# Charger_BQ25713.net
KiCad netlist of a schematic drawn in Altium Designer
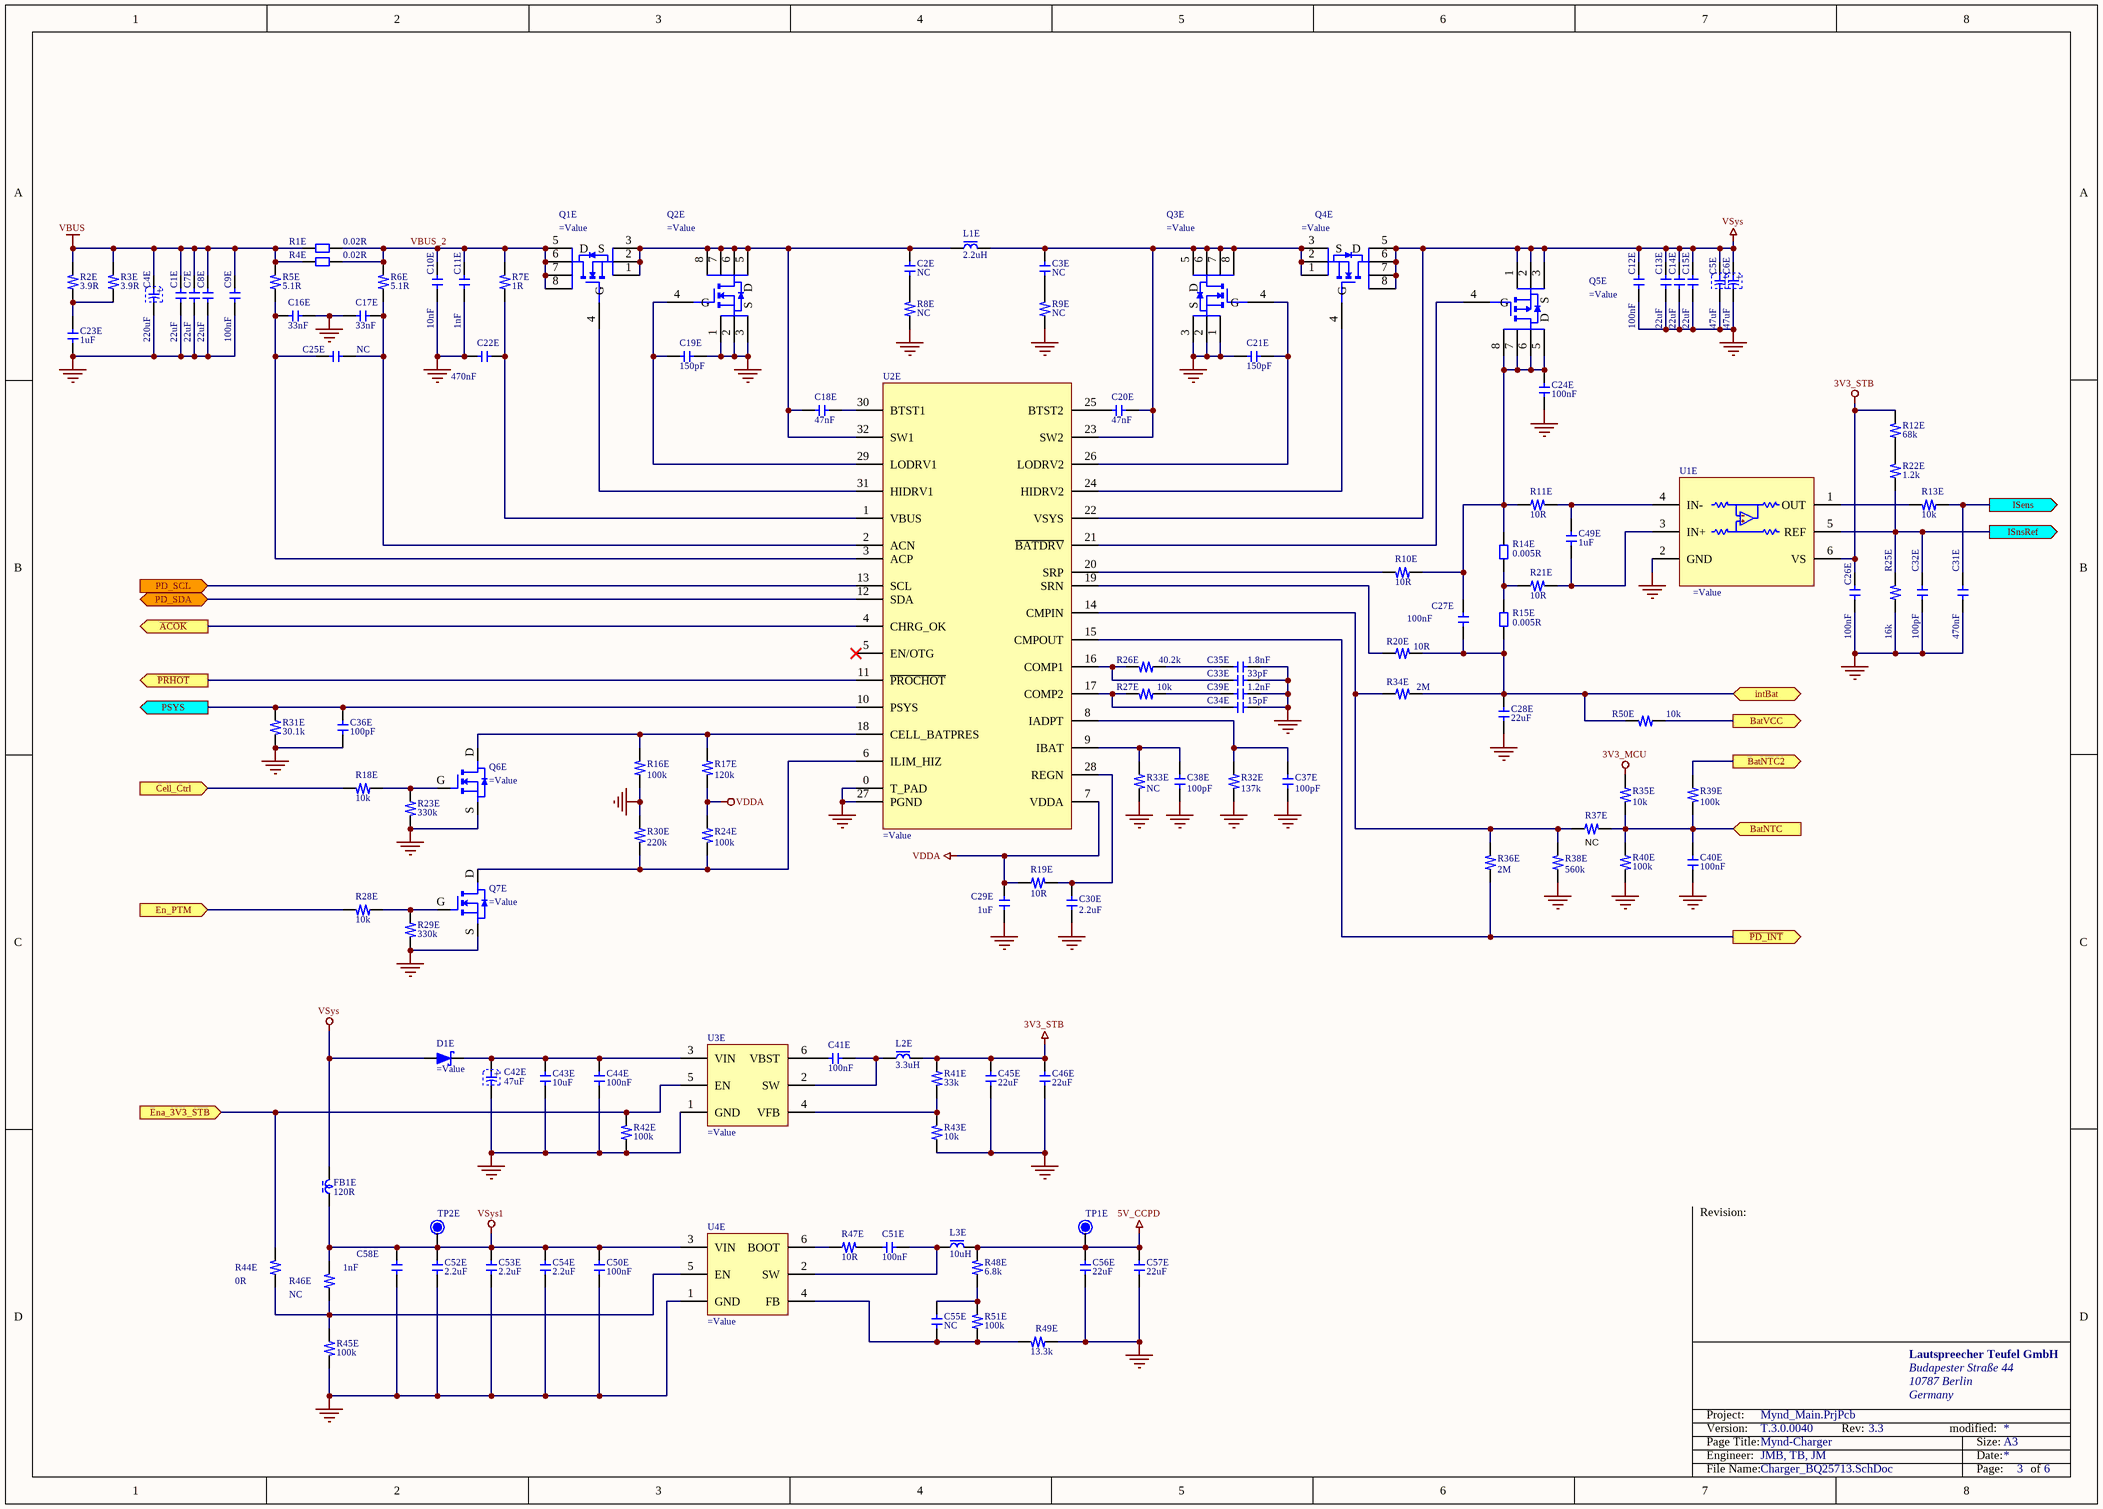
[diagram p0: Charger_BQ25713.SchDoc]

(export (version "E")
  (design (tool "Eeschema 10.0.6"))
  (components
    (comp (ref "C1E")
      (value "22uF")
      (footprint "C1206")
      (description "PSHF SMD M CAP 22uF 25V ±20% 1206 X5R")
      (fields (field (name "MANUFACTURER") "Multi Sourced") (field (name "TOLERANCE") "±20%"))
      (libsource (lib "altium-import") (part "root_3_CAP1_"))
    )
    (comp (ref "C2E")
      (value "NC")
      (footprint "C0603X80")
      (description "PSHF SMD M CAP 30pF 50V ±5% 0603 NPO")
      (fields (field (name "MANUFACTURER") "Multi Sourced") (field (name "TOLERANCE") "±5%"))
      (libsource (lib "altium-import") (part "root_1_CAP1_"))
    )
    (comp (ref "C3E")
      (value "NC")
      (footprint "C0603X80")
      (description "PSHF SMD M CAP 30pF 50V ±5% 0603 NPO")
      (fields (field (name "MANUFACTURER") "Multi Sourced") (field (name "TOLERANCE") "±5%"))
      (libsource (lib "altium-import") (part "root_1_CAP1_"))
    )
    (comp (ref "C4E")
      (value "220uF")
      (footprint "ECAP_SMD_800X1000")
      (description "PS SMD COND ELECT 220uF 35V ±20% 105℃")
      (fields (field (name "MANUFACTURER") "Multi-Sourced") (field (name "TOLERANCE") "±20%"))
      (libsource (lib "altium-import") (part "root_3_ECAP2_"))
    )
    (comp (ref "C5E")
      (value "47uF")
      (footprint "ECAP_SMD_630X540")
      (description "PS SMD COND ELECT 47uF 35V ±20% 105℃")
      (fields (field (name "MANUFACTURER") "Multi-Sourced") (field (name "TOLERANCE") "±20%"))
      (libsource (lib "altium-import") (part "root_3_ECAP2_"))
    )
    (comp (ref "C6E")
      (value "47uF")
      (footprint "ECAP_SMD_630X540")
      (description "PS SMD COND ELECT 47uF 35V ±20% 105℃")
      (fields (field (name "MANUFACTURER") "Multi-Sourced") (field (name "TOLERANCE") "±20%"))
      (libsource (lib "altium-import") (part "root_3_ECAP2_"))
    )
    (comp (ref "C7E")
      (value "22uF")
      (footprint "C1206")
      (description "PSHF SMD M CAP 22uF 25V ±20% 1206 X5R")
      (fields (field (name "MANUFACTURER") "Multi Sourced") (field (name "TOLERANCE") "±20%"))
      (libsource (lib "altium-import") (part "root_1_CAP1_"))
    )
    (comp (ref "C8E")
      (value "22uF")
      (footprint "C1206")
      (description "PSHF SMD M CAP 22uF 25V ±20% 1206 X5R")
      (fields (field (name "MANUFACTURER") "Multi Sourced") (field (name "TOLERANCE") "±20%"))
      (libsource (lib "altium-import") (part "root_1_CAP1_"))
    )
    (comp (ref "C9E")
      (value "100nF")
      (footprint "C0603X100")
      (description "PSHF SMD M CAP 100nF 50V ±10% 0603 X7R")
      (fields (field (name "MANUFACTURER") "Multi Sourced") (field (name "TOLERANCE") "±10%"))
      (libsource (lib "altium-import") (part "root_3_CAP1_"))
    )
    (comp (ref "C10E")
      (value "10nF")
      (footprint "C0603X100")
      (description "PSHF SMD M CAP 10nF 50V ±10% 0603 X7R")
      (fields (field (name "MANUFACTURER") "Multi Sourced") (field (name "TOLERANCE") "±10%"))
      (libsource (lib "altium-import") (part "root_1_CAP1_"))
    )
    (comp (ref "C11E")
      (value "1nF")
      (footprint "C0603X100")
      (description "PSHF SMD M CAP 1nF 50V ±10% 0603 X7R")
      (fields (field (name "MANUFACTURER") "Multi Sourced") (field (name "TOLERANCE") "±10%"))
      (libsource (lib "altium-import") (part "root_3_CAP1_"))
    )
    (comp (ref "C12E")
      (value "100nF")
      (footprint "C0603X100")
      (description "PSHF SMD M CAP 100nF 50V ±10% 0603 X7R")
      (fields (field (name "MANUFACTURER") "Multi Sourced") (field (name "TOLERANCE") "±10%"))
      (libsource (lib "altium-import") (part "root_1_CAP1_"))
    )
    (comp (ref "C13E")
      (value "22uF")
      (footprint "C1206")
      (description "PSHF SMD M CAP 22uF 25V ±20% 1206 X5R")
      (fields (field (name "MANUFACTURER") "Multi Sourced") (field (name "TOLERANCE") "±20%"))
      (libsource (lib "altium-import") (part "root_1_CAP1_"))
    )
    (comp (ref "C14E")
      (value "22uF")
      (footprint "C1206")
      (description "PSHF SMD M CAP 22uF 25V ±20% 1206 X5R")
      (fields (field (name "MANUFACTURER") "Multi Sourced") (field (name "TOLERANCE") "±20%"))
      (libsource (lib "altium-import") (part "root_1_CAP1_"))
    )
    (comp (ref "C15E")
      (value "22uF")
      (footprint "C1206")
      (description "PSHF SMD M CAP 22uF 25V ±20% 1206 X5R")
      (fields (field (name "MANUFACTURER") "Multi Sourced") (field (name "TOLERANCE") "±20%"))
      (libsource (lib "altium-import") (part "root_1_CAP1_"))
    )
    (comp (ref "C16E")
      (value "33nF")
      (footprint "C0603X100")
      (description "PSHF SMD M CAP 33nF 50V ±10% 0603 X7R")
      (fields (field (name "MANUFACTURER") "Multi Sourced") (field (name "TOLERANCE") "±10%"))
      (libsource (lib "altium-import") (part "root_2_CAP1_"))
    )
    (comp (ref "C17E")
      (value "33nF")
      (footprint "C0603X100")
      (description "PSHF SMD M CAP 33nF 50V ±10% 0603 X7R")
      (fields (field (name "MANUFACTURER") "Multi Sourced") (field (name "TOLERANCE") "±10%"))
      (libsource (lib "altium-import") (part "root_0_CAP1_"))
    )
    (comp (ref "C18E")
      (value "47nF")
      (footprint "C0603X100")
      (description "PSHF SMD M CAP 47nF 50V ±10% 0603 X7R")
      (fields (field (name "MANUFACTURER") "Multi Sourced") (field (name "TOLERANCE") "±10"))
      (libsource (lib "altium-import") (part "root_0_CAP1_"))
    )
    (comp (ref "C19E")
      (value "150pF")
      (footprint "C0603X80")
      (description "PSHF SMD M CAP 150pF 50V ±10% 0603 X7R")
      (fields (field (name "MANUFACTURER") "Multi Sourced") (field (name "TOLERANCE") "±10%"))
      (libsource (lib "altium-import") (part "root_2_CAP1_"))
    )
    (comp (ref "C20E")
      (value "47nF")
      (footprint "C0603X100")
      (description "PSHF SMD M CAP 47nF 50V ±10% 0603 X7R")
      (fields (field (name "MANUFACTURER") "Multi Sourced") (field (name "TOLERANCE") "±10"))
      (libsource (lib "altium-import") (part "root_0_CAP1_"))
    )
    (comp (ref "C21E")
      (value "150pF")
      (footprint "C0603X80")
      (description "PSHF SMD M CAP 150pF 50V ±10% 0603 X7R")
      (fields (field (name "MANUFACTURER") "Multi Sourced") (field (name "TOLERANCE") "±10%"))
      (libsource (lib "altium-import") (part "root_2_CAP1_"))
    )
    (comp (ref "C22E")
      (value "470nF")
      (footprint "C0603X100")
      (description "PSHF SMD M CAP 470nF 50V ±10% 0603 X7R")
      (fields (field (name "MANUFACTURER") "Multi Sourced") (field (name "TOLERANCE") "±10%"))
      (libsource (lib "altium-import") (part "root_0_CAP1_"))
    )
    (comp (ref "C23E")
      (value "1uF")
      (footprint "C0805_145")
      (description "PSHF SMD M CAP 1uF 50V ±10% 0805 X7R")
      (fields (field (name "MANUFACTURER") "Multi Sourced") (field (name "TOLERANCE") "±10%"))
      (libsource (lib "altium-import") (part "root_3_CAP1_"))
    )
    (comp (ref "C24E")
      (value "100nF")
      (footprint "C0603X100")
      (description "PSHF SMD M CAP 100nF 50V ±10% 0603 X7R")
      (fields (field (name "MANUFACTURER") "Multi Sourced") (field (name "TOLERANCE") "±10%"))
      (libsource (lib "altium-import") (part "root_3_CAP1_"))
    )
    (comp (ref "C25E")
      (value "NC")
      (footprint "C0603X100")
      (description "PSHF SMD M CAP 10nF 50V ±10% 0603 X7R")
      (fields (field (name "MANUFACTURER") "Multi Sourced") (field (name "TOLERANCE") "±10%"))
      (libsource (lib "altium-import") (part "root_0_CAP1_"))
    )
    (comp (ref "C26E")
      (value "100nF")
      (footprint "C0603X100")
      (description "PSHF SMD M CAP 100nF 50V ±10% 0603 X7R")
      (fields (field (name "MANUFACTURER") "Multi Sourced") (field (name "TOLERANCE") "±10%"))
      (libsource (lib "altium-import") (part "root_1_CAP1_"))
    )
    (comp (ref "C27E")
      (value "100nF")
      (footprint "C0603X100")
      (description "PSHF SMD M CAP 100nF 50V ±10% 0603 X7R")
      (fields (field (name "MANUFACTURER") "Multi Sourced") (field (name "TOLERANCE") "±10%"))
      (libsource (lib "altium-import") (part "root_3_CAP1_"))
    )
    (comp (ref "C28E")
      (value "22uF")
      (footprint "C1206")
      (description "PSHF SMD M CAP 22uF 25V ±20% 1206 X5R")
      (fields (field (name "MANUFACTURER") "Multi Sourced") (field (name "TOLERANCE") "±20%"))
      (libsource (lib "altium-import") (part "root_3_CAP1_"))
    )
    (comp (ref "C29E")
      (value "1uF")
      (footprint "C0603X105")
      (description "PSHF SMD M CAP 1uF 50V ±10% 0603 X7R")
      (fields (field (name "MANUFACTURER") "Multi Sourced") (field (name "TOLERANCE") "±10%"))
      (libsource (lib "altium-import") (part "root_3_CAP1_"))
    )
    (comp (ref "C30E")
      (value "2.2uF")
      (footprint "C0603X105")
      (description "PSHF SMD M CAP 2.2uF 25V ±10% 0603 X5R")
      (fields (field (name "MANUFACTURER") "Multi Sourced") (field (name "TOLERANCE") "±10%"))
      (libsource (lib "altium-import") (part "root_3_CAP1_"))
    )
    (comp (ref "C31E")
      (value "470nF")
      (footprint "C0603X100")
      (description "GPHF SMD M CAP 470nF 50V ±10% 0603 X5R")
      (fields (field (name "MANUFACTURER") "Multi Sourced") (field (name "TOLERANCE") "±10%"))
      (libsource (lib "altium-import") (part "root_1_CAP1_"))
    )
    (comp (ref "C32E")
      (value "100pF")
      (footprint "C0603X80")
      (description "PSHF SMD M CAP 100pF 50V ±10% 0603 X7R")
      (fields (field (name "MANUFACTURER") "Multi Sourced") (field (name "TOLERANCE") "±10%"))
      (libsource (lib "altium-import") (part "root_1_CAP1_"))
    )
    (comp (ref "C33E")
      (value "33pF")
      (footprint "C0603X80")
      (description "PSHF SMD M CAP 33pF 50V ±5% 0603 NPO")
      (fields (field (name "MANUFACTURER") "Multi Sourced") (field (name "TOLERANCE") "±5%"))
      (libsource (lib "altium-import") (part "root_0_mirrored_CAP1_"))
    )
    (comp (ref "C34E")
      (value "15pF")
      (footprint "C0603X80")
      (description "PSHF SMD M CAP 15pF 50V ±5% 0603 NPO")
      (fields (field (name "MANUFACTURER") "Multi Sourced") (field (name "TOLERANCE") "±5%"))
      (libsource (lib "altium-import") (part "root_2_CAP1_"))
    )
    (comp (ref "C35E")
      (value "1.8nF")
      (footprint "C0603X100")
      (description "PSHF SMD M CAP 1.8nF 50V ±10% 0603 X7R")
      (fields (field (name "MANUFACTURER") "Multi Sourced") (field (name "TOLERANCE") "±10%"))
      (libsource (lib "altium-import") (part "root_0_mirrored_CAP1_"))
    )
    (comp (ref "C36E")
      (value "100pF")
      (footprint "C0603X80")
      (description "PSHF SMD M CAP 100pF 50V ±10% 0603 X7R")
      (fields (field (name "MANUFACTURER") "Multi Sourced") (field (name "TOLERANCE") "±10%"))
      (libsource (lib "altium-import") (part "root_3_CAP1_"))
    )
    (comp (ref "C37E")
      (value "100pF")
      (footprint "C0603X80")
      (description "PSHF SMD M CAP 100pF 50V ±10% 0603 X7R")
      (fields (field (name "MANUFACTURER") "Multi Sourced") (field (name "TOLERANCE") "±10%"))
      (libsource (lib "altium-import") (part "root_3_CAP1_"))
    )
    (comp (ref "C38E")
      (value "100pF")
      (footprint "C0603X80")
      (description "PSHF SMD M CAP 100pF 50V ±10% 0603 X7R")
      (fields (field (name "MANUFACTURER") "Multi Sourced") (field (name "TOLERANCE") "±10%"))
      (libsource (lib "altium-import") (part "root_3_CAP1_"))
    )
    (comp (ref "C39E")
      (value "1.2nF")
      (footprint "C0402")
      (description "PSHF SMD M CAP 1.2nF 50V ±10% 0402 X7R")
      (fields (field (name "MANUFACTURER") "Multi Sourced") (field (name "TOLERANCE") "±10%"))
      (libsource (lib "altium-import") (part "root_0_CAP1_"))
    )
    (comp (ref "C40E")
      (value "100nF")
      (footprint "C0603X100")
      (description "PSHF SMD M CAP 100nF 50V ±10% 0603 X7R")
      (fields (field (name "MANUFACTURER") "Multi Sourced") (field (name "TOLERANCE") "±10%"))
      (libsource (lib "altium-import") (part "root_1_CAP1_"))
    )
    (comp (ref "C41E")
      (value "100nF")
      (footprint "C0603X100")
      (description "PSHF SMD M CAP 100nF 50V ±10% 0603 X7R")
      (fields (field (name "MANUFACTURER") "Multi Sourced") (field (name "TOLERANCE") "±10%"))
      (libsource (lib "altium-import") (part "root_0_CAP1_"))
    )
    (comp (ref "C42E")
      (value "47uF")
      (footprint "ECAP_SMD_630X540")
      (description "PS SMD COND ELECT 47uF 35V ±20% 105℃")
      (fields (field (name "MANUFACTURER") "Multi-Sourced") (field (name "TOLERANCE") "±20%"))
      (libsource (lib "altium-import") (part "root_3_ECAP2_"))
    )
    (comp (ref "C43E")
      (value "10uF")
      (footprint "C1206")
      (description "PSHF SMD M CAP 10uF 50V ±10% 1206 X5R")
      (fields (field (name "MANUFACTURER") "Multi Sourced") (field (name "TOLERANCE") "±10%"))
      (libsource (lib "altium-import") (part "root_3_CAP1_"))
    )
    (comp (ref "C44E")
      (value "100nF")
      (footprint "C0603X100")
      (description "PSHF SMD M CAP 100nF 50V ±10% 0603 X7R")
      (fields (field (name "MANUFACTURER") "Multi Sourced") (field (name "TOLERANCE") "±10%"))
      (libsource (lib "altium-import") (part "root_3_CAP1_"))
    )
    (comp (ref "C45E")
      (value "22uF")
      (footprint "C0805_145")
      (description "PSHF SMD M CAP 22uF 10V ±20% 0805 X5R")
      (fields (field (name "MANUFACTURER") "Multi Sourced") (field (name "TOLERANCE") "±20%"))
      (libsource (lib "altium-import") (part "root_3_CAP1_"))
    )
    (comp (ref "C46E")
      (value "22uF")
      (footprint "C0805_145")
      (description "PSHF SMD M CAP 22uF 10V ±20% 0805 X5R")
      (fields (field (name "MANUFACTURER") "Multi Sourced") (field (name "TOLERANCE") "±20%"))
      (libsource (lib "altium-import") (part "root_3_CAP1_"))
    )
    (comp (ref "C49E")
      (value "1uF")
      (footprint "C0603X105")
      (description "GPHF SMD M CAP 1uF 50V ±10% 0603 X7R")
      (fields (field (name "MANUFACTURER") "Multi Sourced") (field (name "TOLERANCE") "±10%"))
      (libsource (lib "altium-import") (part "root_3_CAP1_"))
    )
    (comp (ref "C50E")
      (value "100nF")
      (footprint "C0603X100")
      (description "PSHF SMD M CAP 100nF 50V ±10% 0603 X7R")
      (fields (field (name "MANUFACTURER") "Multi Sourced") (field (name "TOLERANCE") "±10%"))
      (libsource (lib "altium-import") (part "root_3_CAP1_"))
    )
    (comp (ref "C51E")
      (value "100nF")
      (footprint "C0603X100")
      (description "PSHF SMD M CAP 100nF 50V ±10% 0603 X7R")
      (fields (field (name "MANUFACTURER") "Multi Sourced") (field (name "TOLERANCE") "±10%"))
      (libsource (lib "altium-import") (part "root_2_CAP1_"))
    )
    (comp (ref "C52E")
      (value "2.2uF")
      (footprint "C0805_145")
      (description "PSHF SMD M CAP 2.2uF 50V ±10% 0805 X5R")
      (fields (field (name "MANUFACTURER") "Multi Sourced") (field (name "TOLERANCE") "±10%"))
      (libsource (lib "altium-import") (part "root_3_CAP1_"))
    )
    (comp (ref "C53E")
      (value "2.2uF")
      (footprint "C0805_145")
      (description "PSHF SMD M CAP 2.2uF 50V ±10% 0805 X5R")
      (fields (field (name "MANUFACTURER") "Multi Sourced") (field (name "TOLERANCE") "±10%"))
      (libsource (lib "altium-import") (part "root_3_CAP1_"))
    )
    (comp (ref "C54E")
      (value "2.2uF")
      (footprint "C0805_145")
      (description "PSHF SMD M CAP 2.2uF 50V ±10% 0805 X5R")
      (fields (field (name "MANUFACTURER") "Multi Sourced") (field (name "TOLERANCE") "±10%"))
      (libsource (lib "altium-import") (part "root_3_CAP1_"))
    )
    (comp (ref "C55E")
      (value "NC")
      (footprint "C0603X80")
      (description "PSHF SMD M CAP 15pF 50V ±5% 0603 NPO")
      (fields (field (name "MANUFACTURER") "Multi Sourced") (field (name "TOLERANCE") "±5%"))
      (libsource (lib "altium-import") (part "root_3_CAP1_"))
    )
    (comp (ref "C56E")
      (value "22uF")
      (footprint "C0805_145")
      (description "PSHF SMD M CAP 22uF 10V ±20% 0805 X5R")
      (fields (field (name "MANUFACTURER") "Multi Sourced") (field (name "TOLERANCE") "±20%"))
      (libsource (lib "altium-import") (part "root_3_CAP1_"))
    )
    (comp (ref "C57E")
      (value "22uF")
      (footprint "C0805_145")
      (description "PSHF SMD M CAP 22uF 10V ±20% 0805 X5R")
      (fields (field (name "MANUFACTURER") "Multi Sourced") (field (name "TOLERANCE") "±20%"))
      (libsource (lib "altium-import") (part "root_3_CAP1_"))
    )
    (comp (ref "C58E")
      (value "1nF")
      (footprint "C0603X105")
      (description "SMD M CAP 1nF 250V ±10% 0603 X7R")
      (fields (field (name "MANUFACTURER") "Multi Sourced") (field (name "TOLERANCE") "±10%"))
      (libsource (lib "altium-import") (part "root_3_CAP1_"))
    )
    (comp (ref "D1E")
      (value "~")
      (footprint "SOD-123")
      (description "PS SMD DIODE 2P SOD-123 B5819W CJ")
      (fields (field (name "MANUFACTURER") "[CJ]") (field (name "VOLTAGE") "40V"))
      (libsource (lib "altium-import") (part "root_0_DIODE_SCHOTTKY1_"))
    )
    (comp (ref "FB1E")
      (value "120R")
      (footprint "L0805")
      (description "GPHF SMD BEAD 120 OHM 5A 25% 0805")
      (fields (field (name "TOLERANCE") "1:25%") (field (name "MANUFACTURER") "Tai-Tech"))
      (libsource (lib "altium-import") (part "root_3_mirrored_Bead1_"))
    )
    (comp (ref "L1E")
      (value "2.2uH")
      (footprint "IND_SMD_YT_SQU_L118XW108XH40_A")
      (description "SMD INDUCTOR 2.2μH NORM")
      (fields (field (name "MANUFACTURER") "[CET CHAMPIONS]") (field (name "TOLERANCE") "7:20%"))
      (libsource (lib "altium-import") (part "root_0_INDUCTOR1_"))
    )
    (comp (ref "L2E")
      (value "3.3uH")
      (footprint "IND_SMD_SQU_L60XW60XH20")
      (description "SMD INDUCTOR 3.3μH 100KHz NORM")
      (fields (field (name "MANUFACTURER") "TSA") (field (name "TOLERANCE") "7:20%"))
      (libsource (lib "altium-import") (part "root_0_INDUCTOR1_"))
    )
    (comp (ref "L3E")
      (value "10uH")
      (footprint "IND_SMD_YT_SQU_L78XW70XH30")
      (description "GP SMD INDUCTOR 10uH 1MHz 1V NORM")
      (fields (field (name "MANUFACTURER") "[CHAMPIONS]") (field (name "VOLTAGE") "1V"))
      (libsource (lib "altium-import") (part "root_0_INDUCTOR1_"))
    )
    (comp (ref "Q1E")
      (value "~")
      (footprint "DFN8_500X600X100_127_A")
      (description "PSHF SMD FET 8P DFN8 AP4024GEMT-HF APEC")
      (fields (field (name "MANUFACTURER") "APEC") (field (name "VOLTAGE") "30V"))
      (libsource (lib "altium-import") (part "root_1_N-MOS2_8Pin_"))
    )
    (comp (ref "Q2E")
      (value "~")
      (footprint "DFN8_500X600X100_127_A")
      (description "PSHF SMD FET 8P DFN8 AP4024GEMT-HF APEC")
      (fields (field (name "MANUFACTURER") "APEC") (field (name "VOLTAGE") "30V"))
      (libsource (lib "altium-import") (part "root_0_N-MOS2_8Pin_"))
    )
    (comp (ref "Q3E")
      (value "~")
      (footprint "DFN8_500X600X100_127_A")
      (description "PSHF SMD FET 8P DFN8 AP4024GEMT-HF APEC")
      (fields (field (name "MANUFACTURER") "APEC") (field (name "VOLTAGE") "30V"))
      (libsource (lib "altium-import") (part "root_0_mirrored_N-MOS2_8Pin_"))
    )
    (comp (ref "Q4E")
      (value "~")
      (footprint "DFN8_500X600X100_127_A")
      (description "PSHF SMD FET 8P DFN8 AP4024GEMT-HF APEC")
      (fields (field (name "MANUFACTURER") "APEC") (field (name "VOLTAGE") "30V"))
      (libsource (lib "altium-import") (part "root_1_mirrored_N-MOS2_8Pin_"))
    )
    (comp (ref "Q5E")
      (value "~")
      (footprint "DFN8_500X600X100_127_A")
      (description "SMD FET 8P 30V PDFN5X6 SSC8039GN6 SSC")
      (fields (field (name "MANUFACTURER") "SSC") (field (name "VOLTAGE") "30"))
      (libsource (lib "altium-import") (part "root_2_mirrored_P-MOS2_8Pin_"))
    )
    (comp (ref "Q6E")
      (value "~")
      (footprint "SOT23-GSD")
      (description "GP SMD FET 3P SOT23 2N7002K CTE")
      (fields (field (name "MANUFACTURER") "CTE") (field (name "VOLTAGE") "60V"))
      (libsource (lib "altium-import") (part "root_0_N-MOS1_"))
    )
    (comp (ref "Q7E")
      (value "~")
      (footprint "SOT23-GSD")
      (description "GP SMD FET 3P SOT23 2N7002K CTE")
      (fields (field (name "MANUFACTURER") "CTE") (field (name "VOLTAGE") "60V"))
      (libsource (lib "altium-import") (part "root_0_N-MOS1_"))
    )
    (comp (ref "R1E")
      (value "0.02R")
      (footprint "R1206")
      (description "SMD METAL FILM RES. 20mohm 1W 1% 1206 WALTER")
      (fields (field (name "TOLERANCE") "1%") (field (name "MANUFACTURER") "WALTER"))
      (libsource (lib "altium-import") (part "root_0_RES4_"))
    )
    (comp (ref "R2E")
      (value "3.9R")
      (footprint "R0805")
      (description "SMD RES. 3.9Ohm 1/8W 1% 0805")
      (fields (field (name "TOLERANCE") "1%") (field (name "MANUFACTURER") "Multi-Sourced"))
      (libsource (lib "altium-import") (part "root_3_RES1_"))
    )
    (comp (ref "R3E")
      (value "3.9R")
      (footprint "R0805")
      (description "SMD RES. 3.9Ohm 1/8W 1% 0805")
      (fields (field (name "TOLERANCE") "1%") (field (name "MANUFACTURER") "Multi-Sourced"))
      (libsource (lib "altium-import") (part "root_3_RES1_"))
    )
    (comp (ref "R4E")
      (value "0.02R")
      (footprint "R1206")
      (description "SMD METAL FILM RES. 20mohm 1W 1% 1206 WALTER")
      (fields (field (name "TOLERANCE") "1%") (field (name "MANUFACTURER") "WALTER"))
      (libsource (lib "altium-import") (part "root_0_RES4_"))
    )
    (comp (ref "R5E")
      (value "5.1R")
      (footprint "R0603")
      (description "PS SMD RES. 5.1OHM 1/10W 1% 0603")
      (fields (field (name "TOLERANCE") "1%") (field (name "MANUFACTURER") "Multi-Sourced"))
      (libsource (lib "altium-import") (part "root_3_RES1_"))
    )
    (comp (ref "R6E")
      (value "5.1R")
      (footprint "R0603")
      (description "PS SMD RES. 5.1OHM 1/10W 1% 0603")
      (fields (field (name "TOLERANCE") "1%") (field (name "MANUFACTURER") "Multi-Sourced"))
      (libsource (lib "altium-import") (part "root_3_RES1_"))
    )
    (comp (ref "R7E")
      (value "1R")
      (footprint "R0603")
      (description "PS SMD RES. 1Ohm 1/10W 1% 0603")
      (fields (field (name "TOLERANCE") "1%") (field (name "MANUFACTURER") "Multi-Sourced"))
      (libsource (lib "altium-import") (part "root_3_RES1_"))
    )
    (comp (ref "R8E")
      (value "NC")
      (footprint "R0805")
      (description "PS SMD RES. 56OHM 1/8W 5% 0805")
      (fields (field (name "TOLERANCE") "5%") (field (name "MANUFACTURER") "Multi-Sourced"))
      (libsource (lib "altium-import") (part "root_3_RES1_"))
    )
    (comp (ref "R9E")
      (value "NC")
      (footprint "R0805")
      (description "PS SMD RES. 56OHM 1/8W 5% 0805")
      (fields (field (name "TOLERANCE") "5%") (field (name "MANUFACTURER") "Multi-Sourced"))
      (libsource (lib "altium-import") (part "root_3_RES1_"))
    )
    (comp (ref "R10E")
      (value "10R")
      (footprint "R0603")
      (description "PS SMD RES. 10OHM 1/10W 1% 0603")
      (fields (field (name "TOLERANCE") "1%") (field (name "MANUFACTURER") "Multi-Sourced"))
      (libsource (lib "altium-import") (part "root_0_RES1_"))
    )
    (comp (ref "R11E")
      (value "10R")
      (footprint "R0603")
      (description "GPHF SMD RES. 10OHM 1/10W 1% 0603")
      (fields (field (name "TOLERANCE") "1%") (field (name "MANUFACTURER") "Multi-Sourced"))
      (libsource (lib "altium-import") (part "root_2_mirrored_RES1_"))
    )
    (comp (ref "R12E")
      (value "68k")
      (footprint "R0603")
      (description "PS SMD RES. 68KOHM 1/10W 1% 0603")
      (fields (field (name "TOLERANCE") "1%") (field (name "MANUFACTURER") "Multi-Sourced"))
      (libsource (lib "altium-import") (part "root_1_mirrored_RES1_"))
    )
    (comp (ref "R13E")
      (value "10k")
      (footprint "R0603")
      (description "PS SMD RES. 10KOHM 1/10W 1% 0603")
      (fields (field (name "TOLERANCE") "1%") (field (name "MANUFACTURER") "Multi-Sourced"))
      (libsource (lib "altium-import") (part "root_0_mirrored_RES1_"))
    )
    (comp (ref "R14E")
      (value "0.005R")
      (footprint "R1206")
      (description "SMD METAL FILM RES. 5mohm 1W 1% 1206 WALTER")
      (fields (field (name "TOLERANCE") "1%") (field (name "MANUFACTURER") "WALTER"))
      (libsource (lib "altium-import") (part "root_1_RES4_"))
    )
    (comp (ref "R15E")
      (value "0.005R")
      (footprint "R1206")
      (description "SMD METAL FILM RES. 5mohm 1W 1% 1206 WALTER")
      (fields (field (name "TOLERANCE") "1%") (field (name "MANUFACTURER") "WALTER"))
      (libsource (lib "altium-import") (part "root_1_RES4_"))
    )
    (comp (ref "R16E")
      (value "100k")
      (footprint "R0603")
      (description "PS SMD RES. 100KOHM 1/10W 1% 0603")
      (fields (field (name "TOLERANCE") "1%") (field (name "MANUFACTURER") "Multi-Sourced"))
      (libsource (lib "altium-import") (part "root_3_RES1_"))
    )
    (comp (ref "R17E")
      (value "120k")
      (footprint "R0603")
      (description "PS SMD RES. 120Kohm 1/10W 1% 0603")
      (fields (field (name "TOLERANCE") "1%") (field (name "MANUFACTURER") "Multi-Sourced"))
      (libsource (lib "altium-import") (part "root_3_mirrored_RES1_"))
    )
    (comp (ref "R18E")
      (value "10k")
      (footprint "R0603")
      (description "PS SMD RES. 10KOHM 1/10W 1% 0603")
      (fields (field (name "TOLERANCE") "1%") (field (name "MANUFACTURER") "Multi-Sourced"))
      (libsource (lib "altium-import") (part "root_0_RES1_"))
    )
    (comp (ref "R19E")
      (value "10R")
      (footprint "R0603")
      (description "PS SMD RES. 10OHM 1/10W 1% 0603")
      (fields (field (name "TOLERANCE") "1%") (field (name "MANUFACTURER") "Multi-Sourced"))
      (libsource (lib "altium-import") (part "root_2_RES1_"))
    )
    (comp (ref "R20E")
      (value "10R")
      (footprint "R0603")
      (description "PS SMD RES. 10OHM 1/10W 1% 0603")
      (fields (field (name "TOLERANCE") "1%") (field (name "MANUFACTURER") "Multi-Sourced"))
      (libsource (lib "altium-import") (part "root_2_RES1_"))
    )
    (comp (ref "R21E")
      (value "10R")
      (footprint "R0603")
      (description "GPHF SMD RES. 10OHM 1/10W 1% 0603")
      (fields (field (name "TOLERANCE") "1%") (field (name "MANUFACTURER") "Multi-Sourced"))
      (libsource (lib "altium-import") (part "root_2_RES1_"))
    )
    (comp (ref "R22E")
      (value "1.2k")
      (footprint "R0603")
      (description "PS SMD RES. 1.2KOHM 1/10W 1% 0603")
      (fields (field (name "TOLERANCE") "1%") (field (name "MANUFACTURER") "Multi-Sourced"))
      (libsource (lib "altium-import") (part "root_1_mirrored_RES1_"))
    )
    (comp (ref "R23E")
      (value "330k")
      (footprint "R0603")
      (description "PS SMD RES. 330KOHM 1/10W 1% 0603")
      (fields (field (name "TOLERANCE") "1%") (field (name "MANUFACTURER") "Multi-Sourced"))
      (libsource (lib "altium-import") (part "root_1_RES1_"))
    )
    (comp (ref "R24E")
      (value "100k")
      (footprint "R0603")
      (description "PS SMD RES. 100KOHM 1/10W 1% 0603")
      (fields (field (name "TOLERANCE") "1%") (field (name "MANUFACTURER") "Multi-Sourced"))
      (libsource (lib "altium-import") (part "root_3_mirrored_RES1_"))
    )
    (comp (ref "R25E")
      (value "16k")
      (footprint "R0603")
      (description "GPHF SMD RES. 16KOHM 1/10W 1% 0603")
      (fields (field (name "TOLERANCE") "1%") (field (name "MANUFACTURER") "Multi-Sourced"))
      (libsource (lib "altium-import") (part "root_1_mirrored_RES1_"))
    )
    (comp (ref "R26E")
      (value "40.2k")
      (footprint "R0603")
      (description "SMD RES. 40.2KOhm 1/10W 1% 0603")
      (fields (field (name "TOLERANCE") "1%") (field (name "MANUFACTURER") "Multi-Sourced"))
      (libsource (lib "altium-import") (part "root_0_mirrored_RES1_"))
    )
    (comp (ref "R27E")
      (value "10k")
      (footprint "R0603")
      (description "PS SMD RES. 10KOHM 1/10W 1% 0603")
      (fields (field (name "TOLERANCE") "1%") (field (name "MANUFACTURER") "Multi-Sourced"))
      (libsource (lib "altium-import") (part "root_0_RES1_"))
    )
    (comp (ref "R28E")
      (value "10k")
      (footprint "R0603")
      (description "PS SMD RES. 10KOHM 1/10W 1% 0603")
      (fields (field (name "TOLERANCE") "1%") (field (name "MANUFACTURER") "Multi-Sourced"))
      (libsource (lib "altium-import") (part "root_0_RES1_"))
    )
    (comp (ref "R29E")
      (value "330k")
      (footprint "R0603")
      (description "PS SMD RES. 330KOHM 1/10W 1% 0603")
      (fields (field (name "TOLERANCE") "1%") (field (name "MANUFACTURER") "Multi-Sourced"))
      (libsource (lib "altium-import") (part "root_1_RES1_"))
    )
    (comp (ref "R30E")
      (value "220k")
      (footprint "R0603")
      (description "PS SMD RES. 220KOHM 1/10W 1% 0603")
      (fields (field (name "TOLERANCE") "1%") (field (name "MANUFACTURER") "Multi-Sourced"))
      (libsource (lib "altium-import") (part "root_1_RES1_"))
    )
    (comp (ref "R31E")
      (value "30.1k")
      (footprint "R0603")
      (description "PS SMD RES. 30.1KOHM 1/10W 1% 0603")
      (fields (field (name "TOLERANCE") "1%") (field (name "MANUFACTURER") "Multi-Sourced"))
      (libsource (lib "altium-import") (part "root_1_RES1_"))
    )
    (comp (ref "R32E")
      (value "137k")
      (footprint "R0603")
      (description "SMD RES. 137KOhm 1/10W 1% 0603")
      (fields (field (name "TOLERANCE") "1%") (field (name "MANUFACTURER") "Multi-Sourced"))
      (libsource (lib "altium-import") (part "root_1_RES1_"))
    )
    (comp (ref "R33E")
      (value "NC")
      (footprint "R0603")
      (description "PS SMD RES. 100KOHM 1/10W 1% 0603")
      (fields (field (name "TOLERANCE") "1%") (field (name "MANUFACTURER") "Multi-Sourced"))
      (libsource (lib "altium-import") (part "root_1_RES1_"))
    )
    (comp (ref "R34E")
      (value "2M")
      (footprint "R0603")
      (description "PS SMD RES. 2Mohm 1/10W 1% 0603")
      (fields (field (name "TOLERANCE") "1%") (field (name "MANUFACTURER") "Multi-Sourced"))
      (libsource (lib "altium-import") (part "root_2_RES1_"))
    )
    (comp (ref "R35E")
      (value "10k")
      (footprint "R0603")
      (description "PS SMD RES. 10KOHM 1/10W 1% 0603")
      (fields (field (name "TOLERANCE") "1%") (field (name "MANUFACTURER") "Multi-Sourced"))
      (libsource (lib "altium-import") (part "root_1_RES1_"))
    )
    (comp (ref "R36E")
      (value "2M")
      (footprint "R0603")
      (description "PS SMD RES. 2Mohm 1/10W 1% 0603")
      (fields (field (name "TOLERANCE") "1%") (field (name "MANUFACTURER") "Multi-Sourced"))
      (libsource (lib "altium-import") (part "root_3_RES1_"))
    )
    (comp (ref "R37E")
      (value "100k")
      (footprint "R0603")
      (description "PS SMD RES. 100KOHM 1/10W 1% 0603")
      (fields (field (name "TOLERANCE") "1%") (field (name "MANUFACTURER") "Multi-Sourced"))
      (libsource (lib "altium-import") (part "root_2_RES1_"))
    )
    (comp (ref "R38E")
      (value "560k")
      (footprint "R0603")
      (description "PS SMD RES. 560KOHM 1/10W 5% 0603")
      (fields (field (name "TOLERANCE") "1%") (field (name "MANUFACTURER") "Multi-Sourced"))
      (libsource (lib "altium-import") (part "root_3_RES1_"))
    )
    (comp (ref "R39E")
      (value "100k")
      (footprint "R0603")
      (description "PS SMD RES. 100KOHM 1/10W 1% 0603")
      (fields (field (name "TOLERANCE") "1%") (field (name "MANUFACTURER") "Multi-Sourced"))
      (libsource (lib "altium-import") (part "root_1_RES1_"))
    )
    (comp (ref "R40E")
      (value "100k")
      (footprint "R0603")
      (description "PS SMD RES. 100KOHM 1/10W 1% 0603")
      (fields (field (name "TOLERANCE") "1%") (field (name "MANUFACTURER") "Multi-Sourced"))
      (libsource (lib "altium-import") (part "root_1_RES1_"))
    )
    (comp (ref "R41E")
      (value "33k")
      (footprint "R0603")
      (description "PS SMD RES. 33KOHM 1/10W 1% 0603")
      (fields (field (name "TOLERANCE") "1%") (field (name "MANUFACTURER") "Multi-Sourced"))
      (libsource (lib "altium-import") (part "root_1_RES1_"))
    )
    (comp (ref "R42E")
      (value "100k")
      (footprint "R0603")
      (description "PS SMD RES. 100KOHM 1/10W 1% 0603")
      (fields (field (name "TOLERANCE") "1%") (field (name "MANUFACTURER") "Multi-Sourced"))
      (libsource (lib "altium-import") (part "root_3_RES1_"))
    )
    (comp (ref "R43E")
      (value "10k")
      (footprint "R0603")
      (description "PS SMD RES. 10KOHM 1/10W 1% 0603")
      (fields (field (name "TOLERANCE") "1%") (field (name "MANUFACTURER") "Multi-Sourced"))
      (libsource (lib "altium-import") (part "root_3_RES1_"))
    )
    (comp (ref "R44E")
      (value "0R")
      (footprint "R0603")
      (description "PS SMD RES. 0OHM 1/10W 5% 0603")
      (fields (field (name "TOLERANCE") "1%") (field (name "MANUFACTURER") "Multi-Sourced"))
      (libsource (lib "altium-import") (part "root_3_RES1_"))
    )
    (comp (ref "R45E")
      (value "100k")
      (footprint "R0603")
      (description "PS SMD RES. 100KOHM 1/10W 1% 0603")
      (fields (field (name "TOLERANCE") "1%") (field (name "MANUFACTURER") "Multi-Sourced"))
      (libsource (lib "altium-import") (part "root_1_RES1_"))
    )
    (comp (ref "R46E")
      (value "NC")
      (footprint "R0603")
      (description "PS SMD RES. 100KOHM 1/10W 1% 0603")
      (fields (field (name "TOLERANCE") "1%") (field (name "MANUFACTURER") "Multi-Sourced"))
      (libsource (lib "altium-import") (part "root_3_RES1_"))
    )
    (comp (ref "R47E")
      (value "10R")
      (footprint "R0603")
      (description "PS SMD RES. 10OHM 1/10W 1% 0603")
      (fields (field (name "TOLERANCE") "1%") (field (name "MANUFACTURER") "Multi-Sourced"))
      (libsource (lib "altium-import") (part "root_2_RES1_"))
    )
    (comp (ref "R48E")
      (value "6.8k")
      (footprint "R0603")
      (description "GPHF SMD RES. 6.8KOHM 1/10W 1% 0603")
      (fields (field (name "TOLERANCE") "1%") (field (name "MANUFACTURER") "Multi-Sourced"))
      (libsource (lib "altium-import") (part "root_3_RES1_"))
    )
    (comp (ref "R49E")
      (value "13.3k")
      (footprint "R0603")
      (description "PS SMD RES. 13.3KOHM 1/10W 1% 0603")
      (fields (field (name "TOLERANCE") "1%") (field (name "MANUFACTURER") "Multi-Sourced"))
      (libsource (lib "altium-import") (part "root_0_RES1_"))
    )
    (comp (ref "R50E")
      (value "10k")
      (footprint "R0603")
      (description "PS SMD RES. 10KOHM 1/10W 1% 0603")
      (fields (field (name "TOLERANCE") "1%") (field (name "MANUFACTURER") "Multi-Sourced"))
      (libsource (lib "altium-import") (part "root_0_RES1_"))
    )
    (comp (ref "R51E")
      (value "100k")
      (footprint "R0603")
      (description "PS SMD RES. 100KOHM 1/10W 1% 0603")
      (fields (field (name "TOLERANCE") "1%") (field (name "MANUFACTURER") "Multi-Sourced"))
      (libsource (lib "altium-import") (part "root_3_RES1_"))
    )
    (comp (ref "TP1E")
      (value "TP_T_60_40")
      (footprint "TP_T_60_40")
      (description "Test Point")
      (libsource (lib "altium-import") (part "root_1_TP_"))
    )
    (comp (ref "TP2E")
      (value "TP_T_60_40")
      (footprint "TP_T_60_40")
      (description "Test Point")
      (libsource (lib "altium-import") (part "root_1_TP_"))
    )
    (comp (ref "U1E")
      (value "~")
      (footprint "SOT23_6_SC74")
      (description "SMD IC 6P SOT-23 INA181A1IDBVR TI")
      (fields (field (name "MANUFACTURER") "TI") (field (name "PART_NUMBER") "INA181A1IDBVR"))
      (libsource (lib "altium-import") (part "root_0_INA181_"))
    )
    (comp (ref "U2E")
      (value "~")
      (footprint "QFN32_400X400X80_40_P280X280")
      (description "GP SMD IC 32P WQFN BQ25713RSNR TI")
      (fields (field (name "MANUFACTURER") "[TI]") (field (name "PART_NUMBER") "BQ25713RSNR"))
      (libsource (lib "altium-import") (part "root_0_BQ25713_"))
    )
    (comp (ref "U3E")
      (value "~")
      (footprint "SOT23_6_SC74")
      (description "GP SMD IC 6P SOT-23 TPS562201DDCR TI")
      (fields (field (name "MANUFACTURER") "[TI]") (field (name "PART_NUMBER") "TPS562201DDCR"))
      (libsource (lib "altium-import") (part "root_0_TPS56220X_"))
    )
    (comp (ref "U4E")
      (value "~")
      (footprint "SOT23_6_SC74")
      (description "GP SMD IC 6P SOP-23 TPS54302DDCR TI")
      (fields (field (name "MANUFACTURER") "[TI]") (field (name "PART_NUMBER") "TPS54302DDCR"))
      (libsource (lib "altium-import") (part "root_0_TPS54302_"))
    )
  )
  (nets
    (net (code "1") (name "/ACOK") (class "Default")
      (node (ref "U2E") (pin "4") (pinfunction "CHRG_OK_4") (pintype "passive"))
    )
    (net (code "2") (name "/BatNTC") (class "Default")
      (node (ref "C40E") (pin "2") (pinfunction "2_2") (pintype "passive"))
      (node (ref "R35E") (pin "1") (pinfunction "1_1") (pintype "passive"))
      (node (ref "R37E") (pin "1") (pinfunction "1_1") (pintype "passive"))
      (node (ref "R39E") (pin "1") (pinfunction "1_1") (pintype "passive"))
      (node (ref "R40E") (pin "2") (pinfunction "2_2") (pintype "passive"))
    )
    (net (code "3") (name "/BatNTC2") (class "Default")
      (node (ref "R39E") (pin "2") (pinfunction "2_2") (pintype "passive"))
    )
    (net (code "4") (name "/BatVCC") (class "Default")
      (node (ref "R50E") (pin "2") (pinfunction "2_2") (pintype "passive"))
    )
    (net (code "5") (name "/Cell_Ctrl") (class "Default")
      (node (ref "R18E") (pin "1") (pinfunction "1_1") (pintype "passive"))
    )
    (net (code "6") (name "/En_PTM") (class "Default")
      (node (ref "R28E") (pin "1") (pinfunction "1_1") (pintype "passive"))
    )
    (net (code "7") (name "/Ena_3V3_STB") (class "Default")
      (node (ref "R42E") (pin "1") (pinfunction "1_1") (pintype "passive"))
      (node (ref "R44E") (pin "1") (pinfunction "1_1") (pintype "passive"))
      (node (ref "U3E") (pin "5") (pinfunction "EN_5") (pintype "passive"))
    )
    (net (code "8") (name "/ISens") (class "Default")
      (node (ref "C31E") (pin "2") (pinfunction "2_2") (pintype "passive"))
      (node (ref "R13E") (pin "1") (pinfunction "1_1") (pintype "passive"))
    )
    (net (code "9") (name "/ISnsRef") (class "Default")
      (node (ref "C32E") (pin "2") (pinfunction "2_2") (pintype "passive"))
      (node (ref "R22E") (pin "1") (pinfunction "1_1") (pintype "passive"))
      (node (ref "R25E") (pin "2") (pinfunction "2_2") (pintype "passive"))
      (node (ref "U1E") (pin "5") (pinfunction "REF_5") (pintype "passive"))
    )
    (net (code "10") (name "/PD_INT") (class "Default")
      (node (ref "R36E") (pin "2") (pinfunction "2_2") (pintype "passive"))
      (node (ref "U2E") (pin "15") (pinfunction "CMPOUT_15") (pintype "passive"))
    )
    (net (code "11") (name "/PD_SCL") (class "Default")
      (node (ref "U2E") (pin "13") (pinfunction "SCL_13") (pintype "passive"))
    )
    (net (code "12") (name "/PD_SDA") (class "Default")
      (node (ref "U2E") (pin "12") (pinfunction "SDA_12") (pintype "passive"))
    )
    (net (code "13") (name "/PRHOT") (class "Default")
      (node (ref "U2E") (pin "11") (pinfunction "~{PROCHOT}_11") (pintype "passive"))
    )
    (net (code "14") (name "/PSYS") (class "Default")
      (node (ref "C36E") (pin "1") (pinfunction "1_1") (pintype "passive"))
      (node (ref "R31E") (pin "2") (pinfunction "2_2") (pintype "passive"))
      (node (ref "U2E") (pin "10") (pinfunction "PSYS_10") (pintype "passive"))
    )
    (net (code "15") (name "/VBUS_2") (class "Default")
      (node (ref "C10E") (pin "2") (pinfunction "2_2") (pintype "passive"))
      (node (ref "C11E") (pin "1") (pinfunction "1_1") (pintype "passive"))
      (node (ref "Q1E") (pin "5") (pinfunction "D_5") (pintype "passive"))
      (node (ref "Q1E") (pin "6") (pinfunction "D_6") (pintype "passive"))
      (node (ref "Q1E") (pin "7") (pinfunction "D_7") (pintype "passive"))
      (node (ref "Q1E") (pin "8") (pinfunction "D_8") (pintype "passive"))
      (node (ref "R1E") (pin "2") (pinfunction "2_2") (pintype "passive"))
      (node (ref "R4E") (pin "2") (pinfunction "2_2") (pintype "passive"))
      (node (ref "R6E") (pin "1") (pinfunction "1_1") (pintype "passive"))
      (node (ref "R7E") (pin "1") (pinfunction "1_1") (pintype "passive"))
    )
    (net (code "16") (name "/intBat") (class "Default")
      (node (ref "C27E") (pin "2") (pinfunction "2_2") (pintype "passive"))
      (node (ref "C28E") (pin "1") (pinfunction "1_1") (pintype "passive"))
      (node (ref "R15E") (pin "1") (pinfunction "1_1") (pintype "passive"))
      (node (ref "R20E") (pin "1") (pinfunction "1_1") (pintype "passive"))
      (node (ref "R34E") (pin "1") (pinfunction "1_1") (pintype "passive"))
      (node (ref "R50E") (pin "1") (pinfunction "1_1") (pintype "passive"))
    )
    (net (code "17") (name "3V3_MCU") (class "Default")
      (node (ref "R35E") (pin "2") (pinfunction "2_2") (pintype "passive"))
    )
    (net (code "18") (name "3V3_STB") (class "Default")
      (node (ref "C26E") (pin "2") (pinfunction "2_2") (pintype "passive"))
      (node (ref "C45E") (pin "1") (pinfunction "1_1") (pintype "passive"))
      (node (ref "C46E") (pin "1") (pinfunction "1_1") (pintype "passive"))
      (node (ref "L2E") (pin "2") (pinfunction "2_2") (pintype "passive"))
      (node (ref "R12E") (pin "2") (pinfunction "2_2") (pintype "passive"))
      (node (ref "R41E") (pin "2") (pinfunction "2_2") (pintype "passive"))
      (node (ref "U1E") (pin "6") (pinfunction "VS_6") (pintype "passive"))
    )
    (net (code "19") (name "5V_CCPD") (class "Default")
      (node (ref "C56E") (pin "1") (pinfunction "1_1") (pintype "passive"))
      (node (ref "C57E") (pin "1") (pinfunction "1_1") (pintype "passive"))
      (node (ref "L3E") (pin "2") (pinfunction "2_2") (pintype "passive"))
      (node (ref "R48E") (pin "1") (pinfunction "1_1") (pintype "passive"))
      (node (ref "TP1E") (pin "1") (pinfunction "1_1") (pintype "passive"))
    )
    (net (code "20") (name "GND") (class "Default")
      (node (ref "C10E") (pin "1") (pinfunction "1_1") (pintype "passive"))
      (node (ref "C11E") (pin "2") (pinfunction "2_2") (pintype "passive"))
      (node (ref "C12E") (pin "1") (pinfunction "1_1") (pintype "passive"))
      (node (ref "C13E") (pin "1") (pinfunction "1_1") (pintype "passive"))
      (node (ref "C14E") (pin "1") (pinfunction "1_1") (pintype "passive"))
      (node (ref "C15E") (pin "1") (pinfunction "1_1") (pintype "passive"))
      (node (ref "C16E") (pin "1") (pinfunction "1_1") (pintype "passive"))
      (node (ref "C17E") (pin "1") (pinfunction "1_1") (pintype "passive"))
      (node (ref "C19E") (pin "1") (pinfunction "1_1") (pintype "passive"))
      (node (ref "C1E") (pin "2") (pinfunction "2_2") (pintype "passive"))
      (node (ref "C21E") (pin "2") (pinfunction "2_2") (pintype "passive"))
      (node (ref "C22E") (pin "1") (pinfunction "1_1") (pintype "passive"))
      (node (ref "C23E") (pin "2") (pinfunction "2_2") (pintype "passive"))
      (node (ref "C24E") (pin "2") (pinfunction "2_2") (pintype "passive"))
      (node (ref "C26E") (pin "1") (pinfunction "1_1") (pintype "passive"))
      (node (ref "C28E") (pin "2") (pinfunction "2_2") (pintype "passive"))
      (node (ref "C29E") (pin "2") (pinfunction "2_2") (pintype "passive"))
      (node (ref "C30E") (pin "2") (pinfunction "2_2") (pintype "passive"))
      (node (ref "C31E") (pin "1") (pinfunction "1_1") (pintype "passive"))
      (node (ref "C32E") (pin "1") (pinfunction "1_1") (pintype "passive"))
      (node (ref "C33E") (pin "1") (pinfunction "1_1") (pintype "passive"))
      (node (ref "C34E") (pin "1") (pinfunction "1_1") (pintype "passive"))
      (node (ref "C35E") (pin "1") (pinfunction "1_1") (pintype "passive"))
      (node (ref "C36E") (pin "2") (pinfunction "2_2") (pintype "passive"))
      (node (ref "C37E") (pin "2") (pinfunction "2_2") (pintype "passive"))
      (node (ref "C38E") (pin "2") (pinfunction "2_2") (pintype "passive"))
      (node (ref "C39E") (pin "2") (pinfunction "2_2") (pintype "passive"))
      (node (ref "C40E") (pin "1") (pinfunction "1_1") (pintype "passive"))
      (node (ref "C42E") (pin "2") (pinfunction "2_2") (pintype "passive"))
      (node (ref "C43E") (pin "2") (pinfunction "2_2") (pintype "passive"))
      (node (ref "C44E") (pin "2") (pinfunction "2_2") (pintype "passive"))
      (node (ref "C45E") (pin "2") (pinfunction "2_2") (pintype "passive"))
      (node (ref "C46E") (pin "2") (pinfunction "2_2") (pintype "passive"))
      (node (ref "C4E") (pin "2") (pinfunction "2_2") (pintype "passive"))
      (node (ref "C50E") (pin "2") (pinfunction "2_2") (pintype "passive"))
      (node (ref "C52E") (pin "2") (pinfunction "2_2") (pintype "passive"))
      (node (ref "C53E") (pin "2") (pinfunction "2_2") (pintype "passive"))
      (node (ref "C54E") (pin "2") (pinfunction "2_2") (pintype "passive"))
      (node (ref "C56E") (pin "2") (pinfunction "2_2") (pintype "passive"))
      (node (ref "C57E") (pin "2") (pinfunction "2_2") (pintype "passive"))
      (node (ref "C58E") (pin "2") (pinfunction "2_2") (pintype "passive"))
      (node (ref "C5E") (pin "2") (pinfunction "2_2") (pintype "passive"))
      (node (ref "C6E") (pin "2") (pinfunction "2_2") (pintype "passive"))
      (node (ref "C7E") (pin "1") (pinfunction "1_1") (pintype "passive"))
      (node (ref "C8E") (pin "1") (pinfunction "1_1") (pintype "passive"))
      (node (ref "C9E") (pin "2") (pinfunction "2_2") (pintype "passive"))
      (node (ref "Q2E") (pin "1") (pinfunction "S_1") (pintype "passive"))
      (node (ref "Q2E") (pin "2") (pinfunction "S_2") (pintype "passive"))
      (node (ref "Q2E") (pin "3") (pinfunction "S_3") (pintype "passive"))
      (node (ref "Q3E") (pin "1") (pinfunction "S_1") (pintype "passive"))
      (node (ref "Q3E") (pin "2") (pinfunction "S_2") (pintype "passive"))
      (node (ref "Q3E") (pin "3") (pinfunction "S_3") (pintype "passive"))
      (node (ref "Q6E") (pin "S") (pinfunction "S_S") (pintype "passive"))
      (node (ref "Q7E") (pin "S") (pinfunction "S_S") (pintype "passive"))
      (node (ref "R16E") (pin "2") (pinfunction "2_2") (pintype "passive"))
      (node (ref "R23E") (pin "1") (pinfunction "1_1") (pintype "passive"))
      (node (ref "R25E") (pin "1") (pinfunction "1_1") (pintype "passive"))
      (node (ref "R29E") (pin "1") (pinfunction "1_1") (pintype "passive"))
      (node (ref "R30E") (pin "2") (pinfunction "2_2") (pintype "passive"))
      (node (ref "R31E") (pin "1") (pinfunction "1_1") (pintype "passive"))
      (node (ref "R32E") (pin "1") (pinfunction "1_1") (pintype "passive"))
      (node (ref "R33E") (pin "1") (pinfunction "1_1") (pintype "passive"))
      (node (ref "R38E") (pin "2") (pinfunction "2_2") (pintype "passive"))
      (node (ref "R40E") (pin "1") (pinfunction "1_1") (pintype "passive"))
      (node (ref "R42E") (pin "2") (pinfunction "2_2") (pintype "passive"))
      (node (ref "R43E") (pin "2") (pinfunction "2_2") (pintype "passive"))
      (node (ref "R45E") (pin "1") (pinfunction "1_1") (pintype "passive"))
      (node (ref "R49E") (pin "2") (pinfunction "2_2") (pintype "passive"))
      (node (ref "R8E") (pin "2") (pinfunction "2_2") (pintype "passive"))
      (node (ref "R9E") (pin "2") (pinfunction "2_2") (pintype "passive"))
      (node (ref "U1E") (pin "2") (pinfunction "GND_2") (pintype "passive"))
      (node (ref "U2E") (pin "0") (pinfunction "T_PAD_0") (pintype "passive"))
      (node (ref "U2E") (pin "27") (pinfunction "PGND_27") (pintype "passive"))
      (node (ref "U3E") (pin "1") (pinfunction "GND_1") (pintype "passive"))
      (node (ref "U4E") (pin "1") (pinfunction "GND_1") (pintype "passive"))
    )
    (net (code "21") (name "Net-(C2E-Pad1)") (class "Default")
      (node (ref "C2E") (pin "1") (pinfunction "1_1") (pintype "passive"))
      (node (ref "R8E") (pin "1") (pinfunction "1_1") (pintype "passive"))
    )
    (net (code "22") (name "Net-(C3E-Pad1)") (class "Default")
      (node (ref "C3E") (pin "1") (pinfunction "1_1") (pintype "passive"))
      (node (ref "R9E") (pin "1") (pinfunction "1_1") (pintype "passive"))
    )
    (net (code "23") (name "Net-(C23E-Pad1)") (class "Default")
      (node (ref "C23E") (pin "1") (pinfunction "1_1") (pintype "passive"))
      (node (ref "R2E") (pin "2") (pinfunction "2_2") (pintype "passive"))
      (node (ref "R3E") (pin "2") (pinfunction "2_2") (pintype "passive"))
    )
    (net (code "24") (name "Net-(C24E-Pad1)") (class "Default")
      (node (ref "C24E") (pin "1") (pinfunction "1_1") (pintype "passive"))
      (node (ref "C27E") (pin "1") (pinfunction "1_1") (pintype "passive"))
      (node (ref "Q5E") (pin "5") (pinfunction "D_5") (pintype "passive"))
      (node (ref "Q5E") (pin "6") (pinfunction "D_6") (pintype "passive"))
      (node (ref "Q5E") (pin "7") (pinfunction "D_7") (pintype "passive"))
      (node (ref "Q5E") (pin "8") (pinfunction "D_8") (pintype "passive"))
      (node (ref "R10E") (pin "2") (pinfunction "2_2") (pintype "passive"))
      (node (ref "R11E") (pin "1") (pinfunction "1_1") (pintype "passive"))
      (node (ref "R14E") (pin "2") (pinfunction "2_2") (pintype "passive"))
    )
    (net (code "25") (name "Net-(C35E-Pad2)") (class "Default")
      (node (ref "C35E") (pin "2") (pinfunction "2_2") (pintype "passive"))
      (node (ref "R26E") (pin "1") (pinfunction "1_1") (pintype "passive"))
    )
    (net (code "26") (name "Net-(C39E-Pad1)") (class "Default")
      (node (ref "C39E") (pin "1") (pinfunction "1_1") (pintype "passive"))
      (node (ref "R27E") (pin "2") (pinfunction "2_2") (pintype "passive"))
    )
    (net (code "27") (name "Net-(C51E-Pad2)") (class "Default")
      (node (ref "C51E") (pin "2") (pinfunction "2_2") (pintype "passive"))
      (node (ref "R47E") (pin "1") (pinfunction "1_1") (pintype "passive"))
    )
    (net (code "28") (name "Net-(C55E-Pad1)") (class "Default")
      (node (ref "C55E") (pin "1") (pinfunction "1_1") (pintype "passive"))
      (node (ref "R48E") (pin "2") (pinfunction "2_2") (pintype "passive"))
      (node (ref "R51E") (pin "1") (pinfunction "1_1") (pintype "passive"))
    )
    (net (code "29") (name "Net-(Q1E-G)") (class "Default")
      (node (ref "Q1E") (pin "4") (pinfunction "G_4") (pintype "passive"))
      (node (ref "U2E") (pin "31") (pinfunction "HIDRV1_31") (pintype "passive"))
    )
    (net (code "30") (name "Net-(Q2E-G)") (class "Default")
      (node (ref "C19E") (pin "2") (pinfunction "2_2") (pintype "passive"))
      (node (ref "Q2E") (pin "4") (pinfunction "G_4") (pintype "passive"))
      (node (ref "U2E") (pin "29") (pinfunction "LODRV1_29") (pintype "passive"))
    )
    (net (code "31") (name "Net-(Q3E-G)") (class "Default")
      (node (ref "C21E") (pin "1") (pinfunction "1_1") (pintype "passive"))
      (node (ref "Q3E") (pin "4") (pinfunction "G_4") (pintype "passive"))
      (node (ref "U2E") (pin "26") (pinfunction "LODRV2_26") (pintype "passive"))
    )
    (net (code "32") (name "Net-(Q4E-G)") (class "Default")
      (node (ref "Q4E") (pin "4") (pinfunction "G_4") (pintype "passive"))
      (node (ref "U2E") (pin "24") (pinfunction "HIDRV2_24") (pintype "passive"))
    )
    (net (code "33") (name "Net-(Q5E-G)") (class "Default")
      (node (ref "Q5E") (pin "4") (pinfunction "G_4") (pintype "passive"))
      (node (ref "U2E") (pin "21") (pinfunction "~{BATDRV}_21") (pintype "passive"))
    )
    (net (code "34") (name "Net-(Q6E-PadG)") (class "Default")
      (node (ref "Q6E") (pin "G") (pinfunction "G_G") (pintype "passive"))
      (node (ref "R18E") (pin "2") (pinfunction "2_2") (pintype "passive"))
      (node (ref "R23E") (pin "2") (pinfunction "2_2") (pintype "passive"))
    )
    (net (code "35") (name "Net-(Q7E-PadG)") (class "Default")
      (node (ref "Q7E") (pin "G") (pinfunction "G_G") (pintype "passive"))
      (node (ref "R28E") (pin "2") (pinfunction "2_2") (pintype "passive"))
      (node (ref "R29E") (pin "2") (pinfunction "2_2") (pintype "passive"))
    )
    (net (code "36") (name "Net-(R12E-Pad1)") (class "Default")
      (node (ref "R12E") (pin "1") (pinfunction "1_1") (pintype "passive"))
      (node (ref "R22E") (pin "2") (pinfunction "2_2") (pintype "passive"))
    )
    (net (code "37") (name "Net-(R14E-Pad1)") (class "Default")
      (node (ref "R14E") (pin "1") (pinfunction "1_1") (pintype "passive"))
      (node (ref "R15E") (pin "2") (pinfunction "2_2") (pintype "passive"))
      (node (ref "R21E") (pin "2") (pinfunction "2_2") (pintype "passive"))
    )
    (net (code "38") (name "Net-(U1E-IN+)") (class "Default")
      (node (ref "C49E") (pin "2") (pinfunction "2_2") (pintype "passive"))
      (node (ref "R21E") (pin "1") (pinfunction "1_1") (pintype "passive"))
      (node (ref "U1E") (pin "3") (pinfunction "IN+_3") (pintype "passive"))
    )
    (net (code "39") (name "Net-(U1E-IN-)") (class "Default")
      (node (ref "C49E") (pin "1") (pinfunction "1_1") (pintype "passive"))
      (node (ref "R11E") (pin "2") (pinfunction "2_2") (pintype "passive"))
      (node (ref "U1E") (pin "4") (pinfunction "IN-_4") (pintype "passive"))
    )
    (net (code "40") (name "Net-(U1E-OUT)") (class "Default")
      (node (ref "R13E") (pin "2") (pinfunction "2_2") (pintype "passive"))
      (node (ref "U1E") (pin "1") (pinfunction "OUT_1") (pintype "passive"))
    )
    (net (code "41") (name "Net-(U2E-ACN)") (class "Default")
      (node (ref "C17E") (pin "2") (pinfunction "2_2") (pintype "passive"))
      (node (ref "C25E") (pin "2") (pinfunction "2_2") (pintype "passive"))
      (node (ref "R6E") (pin "2") (pinfunction "2_2") (pintype "passive"))
      (node (ref "U2E") (pin "2") (pinfunction "ACN_2") (pintype "passive"))
    )
    (net (code "42") (name "Net-(U2E-ACP)") (class "Default")
      (node (ref "C16E") (pin "2") (pinfunction "2_2") (pintype "passive"))
      (node (ref "C25E") (pin "1") (pinfunction "1_1") (pintype "passive"))
      (node (ref "R5E") (pin "2") (pinfunction "2_2") (pintype "passive"))
      (node (ref "U2E") (pin "3") (pinfunction "ACP_3") (pintype "passive"))
    )
    (net (code "43") (name "Net-(U2E-BTST1)") (class "Default")
      (node (ref "C18E") (pin "2") (pinfunction "2_2") (pintype "passive"))
      (node (ref "U2E") (pin "30") (pinfunction "BTST1_30") (pintype "passive"))
    )
    (net (code "44") (name "Net-(U2E-BTST2)") (class "Default")
      (node (ref "C20E") (pin "1") (pinfunction "1_1") (pintype "passive"))
      (node (ref "U2E") (pin "25") (pinfunction "BTST2_25") (pintype "passive"))
    )
    (net (code "45") (name "Net-(U2E-CELL_BATPRES)") (class "Default")
      (node (ref "Q6E") (pin "D") (pinfunction "D_D") (pintype "passive"))
      (node (ref "R16E") (pin "1") (pinfunction "1_1") (pintype "passive"))
      (node (ref "R17E") (pin "1") (pinfunction "1_1") (pintype "passive"))
      (node (ref "U2E") (pin "18") (pinfunction "CELL_BATPRES_18") (pintype "passive"))
    )
    (net (code "46") (name "Net-(U2E-CMPIN)") (class "Default")
      (node (ref "R34E") (pin "2") (pinfunction "2_2") (pintype "passive"))
      (node (ref "R36E") (pin "1") (pinfunction "1_1") (pintype "passive"))
      (node (ref "R37E") (pin "2") (pinfunction "2_2") (pintype "passive"))
      (node (ref "R38E") (pin "1") (pinfunction "1_1") (pintype "passive"))
      (node (ref "U2E") (pin "14") (pinfunction "CMPIN_14") (pintype "passive"))
    )
    (net (code "47") (name "Net-(U2E-COMP1)") (class "Default")
      (node (ref "C33E") (pin "2") (pinfunction "2_2") (pintype "passive"))
      (node (ref "R26E") (pin "2") (pinfunction "2_2") (pintype "passive"))
      (node (ref "U2E") (pin "16") (pinfunction "COMP1_16") (pintype "passive"))
    )
    (net (code "48") (name "Net-(U2E-COMP2)") (class "Default")
      (node (ref "C34E") (pin "2") (pinfunction "2_2") (pintype "passive"))
      (node (ref "R27E") (pin "1") (pinfunction "1_1") (pintype "passive"))
      (node (ref "U2E") (pin "17") (pinfunction "COMP2_17") (pintype "passive"))
    )
    (net (code "49") (name "Net-(U2E-IADPT)") (class "Default")
      (node (ref "C37E") (pin "1") (pinfunction "1_1") (pintype "passive"))
      (node (ref "R32E") (pin "2") (pinfunction "2_2") (pintype "passive"))
      (node (ref "U2E") (pin "8") (pinfunction "IADPT_8") (pintype "passive"))
    )
    (net (code "50") (name "Net-(U2E-IBAT)") (class "Default")
      (node (ref "C38E") (pin "1") (pinfunction "1_1") (pintype "passive"))
      (node (ref "R33E") (pin "2") (pinfunction "2_2") (pintype "passive"))
      (node (ref "U2E") (pin "9") (pinfunction "IBAT_9") (pintype "passive"))
    )
    (net (code "51") (name "Net-(U2E-ILIM_HIZ)") (class "Default")
      (node (ref "Q7E") (pin "D") (pinfunction "D_D") (pintype "passive"))
      (node (ref "R24E") (pin "2") (pinfunction "2_2") (pintype "passive"))
      (node (ref "R30E") (pin "1") (pinfunction "1_1") (pintype "passive"))
      (node (ref "U2E") (pin "6") (pinfunction "ILIM_HIZ_6") (pintype "passive"))
    )
    (net (code "52") (name "Net-(U2E-REGN)") (class "Default")
      (node (ref "C30E") (pin "1") (pinfunction "1_1") (pintype "passive"))
      (node (ref "R19E") (pin "1") (pinfunction "1_1") (pintype "passive"))
      (node (ref "U2E") (pin "28") (pinfunction "REGN_28") (pintype "passive"))
    )
    (net (code "53") (name "Net-(U2E-SRN)") (class "Default")
      (node (ref "R20E") (pin "2") (pinfunction "2_2") (pintype "passive"))
      (node (ref "U2E") (pin "19") (pinfunction "SRN_19") (pintype "passive"))
    )
    (net (code "54") (name "Net-(U2E-SRP)") (class "Default")
      (node (ref "R10E") (pin "1") (pinfunction "1_1") (pintype "passive"))
      (node (ref "U2E") (pin "20") (pinfunction "SRP_20") (pintype "passive"))
    )
    (net (code "55") (name "Net-(U2E-SW1)") (class "Default")
      (node (ref "C18E") (pin "1") (pinfunction "1_1") (pintype "passive"))
      (node (ref "C2E") (pin "2") (pinfunction "2_2") (pintype "passive"))
      (node (ref "L1E") (pin "1") (pinfunction "1_1") (pintype "passive"))
      (node (ref "Q1E") (pin "1") (pinfunction "S_1") (pintype "passive"))
      (node (ref "Q1E") (pin "2") (pinfunction "S_2") (pintype "passive"))
      (node (ref "Q1E") (pin "3") (pinfunction "S_3") (pintype "passive"))
      (node (ref "Q2E") (pin "5") (pinfunction "D_5") (pintype "passive"))
      (node (ref "Q2E") (pin "6") (pinfunction "D_6") (pintype "passive"))
      (node (ref "Q2E") (pin "7") (pinfunction "D_7") (pintype "passive"))
      (node (ref "Q2E") (pin "8") (pinfunction "D_8") (pintype "passive"))
      (node (ref "U2E") (pin "32") (pinfunction "SW1_32") (pintype "passive"))
    )
    (net (code "56") (name "Net-(U2E-SW2)") (class "Default")
      (node (ref "C20E") (pin "2") (pinfunction "2_2") (pintype "passive"))
      (node (ref "C3E") (pin "2") (pinfunction "2_2") (pintype "passive"))
      (node (ref "L1E") (pin "2") (pinfunction "2_2") (pintype "passive"))
      (node (ref "Q3E") (pin "5") (pinfunction "D_5") (pintype "passive"))
      (node (ref "Q3E") (pin "6") (pinfunction "D_6") (pintype "passive"))
      (node (ref "Q3E") (pin "7") (pinfunction "D_7") (pintype "passive"))
      (node (ref "Q3E") (pin "8") (pinfunction "D_8") (pintype "passive"))
      (node (ref "Q4E") (pin "1") (pinfunction "S_1") (pintype "passive"))
      (node (ref "Q4E") (pin "2") (pinfunction "S_2") (pintype "passive"))
      (node (ref "Q4E") (pin "3") (pinfunction "S_3") (pintype "passive"))
      (node (ref "U2E") (pin "23") (pinfunction "SW2_23") (pintype "passive"))
    )
    (net (code "57") (name "Net-(U2E-VBUS)") (class "Default")
      (node (ref "C22E") (pin "2") (pinfunction "2_2") (pintype "passive"))
      (node (ref "R7E") (pin "2") (pinfunction "2_2") (pintype "passive"))
      (node (ref "U2E") (pin "1") (pinfunction "VBUS_1") (pintype "passive"))
    )
    (net (code "58") (name "Net-(U3E-SW)") (class "Default")
      (node (ref "C41E") (pin "2") (pinfunction "2_2") (pintype "passive"))
      (node (ref "L2E") (pin "1") (pinfunction "1_1") (pintype "passive"))
      (node (ref "U3E") (pin "2") (pinfunction "SW_2") (pintype "passive"))
    )
    (net (code "59") (name "Net-(U3E-VBST)") (class "Default")
      (node (ref "C41E") (pin "1") (pinfunction "1_1") (pintype "passive"))
      (node (ref "U3E") (pin "6") (pinfunction "VBST_6") (pintype "passive"))
    )
    (net (code "60") (name "Net-(U3E-VFB)") (class "Default")
      (node (ref "R41E") (pin "1") (pinfunction "1_1") (pintype "passive"))
      (node (ref "R43E") (pin "1") (pinfunction "1_1") (pintype "passive"))
      (node (ref "U3E") (pin "4") (pinfunction "VFB_4") (pintype "passive"))
    )
    (net (code "61") (name "Net-(U3E-VIN)") (class "Default")
      (node (ref "C42E") (pin "1") (pinfunction "1_1") (pintype "passive"))
      (node (ref "C43E") (pin "1") (pinfunction "1_1") (pintype "passive"))
      (node (ref "C44E") (pin "1") (pinfunction "1_1") (pintype "passive"))
      (node (ref "D1E") (pin "K") (pinfunction "K_K") (pintype "passive"))
      (node (ref "U3E") (pin "3") (pinfunction "VIN_3") (pintype "passive"))
    )
    (net (code "62") (name "Net-(U4E-BOOT)") (class "Default")
      (node (ref "R47E") (pin "2") (pinfunction "2_2") (pintype "passive"))
      (node (ref "U4E") (pin "6") (pinfunction "BOOT_6") (pintype "passive"))
    )
    (net (code "63") (name "Net-(U4E-EN)") (class "Default")
      (node (ref "R44E") (pin "2") (pinfunction "2_2") (pintype "passive"))
      (node (ref "R45E") (pin "2") (pinfunction "2_2") (pintype "passive"))
      (node (ref "R46E") (pin "2") (pinfunction "2_2") (pintype "passive"))
      (node (ref "U4E") (pin "5") (pinfunction "EN_5") (pintype "passive"))
    )
    (net (code "64") (name "Net-(U4E-FB)") (class "Default")
      (node (ref "C55E") (pin "2") (pinfunction "2_2") (pintype "passive"))
      (node (ref "R49E") (pin "1") (pinfunction "1_1") (pintype "passive"))
      (node (ref "R51E") (pin "2") (pinfunction "2_2") (pintype "passive"))
      (node (ref "U4E") (pin "4") (pinfunction "FB_4") (pintype "passive"))
    )
    (net (code "65") (name "Net-(U4E-SW)") (class "Default")
      (node (ref "C51E") (pin "1") (pinfunction "1_1") (pintype "passive"))
      (node (ref "L3E") (pin "1") (pinfunction "1_1") (pintype "passive"))
      (node (ref "U4E") (pin "2") (pinfunction "SW_2") (pintype "passive"))
    )
    (net (code "66") (name "VBUS") (class "Default")
      (node (ref "C1E") (pin "1") (pinfunction "1_1") (pintype "passive"))
      (node (ref "C4E") (pin "1") (pinfunction "1_1") (pintype "passive"))
      (node (ref "C7E") (pin "2") (pinfunction "2_2") (pintype "passive"))
      (node (ref "C8E") (pin "2") (pinfunction "2_2") (pintype "passive"))
      (node (ref "C9E") (pin "1") (pinfunction "1_1") (pintype "passive"))
      (node (ref "R1E") (pin "1") (pinfunction "1_1") (pintype "passive"))
      (node (ref "R2E") (pin "1") (pinfunction "1_1") (pintype "passive"))
      (node (ref "R3E") (pin "1") (pinfunction "1_1") (pintype "passive"))
      (node (ref "R4E") (pin "1") (pinfunction "1_1") (pintype "passive"))
      (node (ref "R5E") (pin "1") (pinfunction "1_1") (pintype "passive"))
    )
    (net (code "67") (name "VDDA") (class "Default")
      (node (ref "C29E") (pin "1") (pinfunction "1_1") (pintype "passive"))
      (node (ref "R17E") (pin "2") (pinfunction "2_2") (pintype "passive"))
      (node (ref "R19E") (pin "2") (pinfunction "2_2") (pintype "passive"))
      (node (ref "R24E") (pin "1") (pinfunction "1_1") (pintype "passive"))
      (node (ref "U2E") (pin "7") (pinfunction "VDDA_7") (pintype "passive"))
    )
    (net (code "68") (name "VSys") (class "Default")
      (node (ref "C12E") (pin "2") (pinfunction "2_2") (pintype "passive"))
      (node (ref "C13E") (pin "2") (pinfunction "2_2") (pintype "passive"))
      (node (ref "C14E") (pin "2") (pinfunction "2_2") (pintype "passive"))
      (node (ref "C15E") (pin "2") (pinfunction "2_2") (pintype "passive"))
      (node (ref "C5E") (pin "1") (pinfunction "1_1") (pintype "passive"))
      (node (ref "C6E") (pin "1") (pinfunction "1_1") (pintype "passive"))
      (node (ref "D1E") (pin "A") (pinfunction "A_A") (pintype "passive"))
      (node (ref "FB1E") (pin "1") (pinfunction "1_1") (pintype "passive"))
      (node (ref "Q4E") (pin "5") (pinfunction "D_5") (pintype "passive"))
      (node (ref "Q4E") (pin "6") (pinfunction "D_6") (pintype "passive"))
      (node (ref "Q4E") (pin "7") (pinfunction "D_7") (pintype "passive"))
      (node (ref "Q4E") (pin "8") (pinfunction "D_8") (pintype "passive"))
      (node (ref "Q5E") (pin "1") (pinfunction "S_1") (pintype "passive"))
      (node (ref "Q5E") (pin "2") (pinfunction "S_2") (pintype "passive"))
      (node (ref "Q5E") (pin "3") (pinfunction "S_3") (pintype "passive"))
      (node (ref "U2E") (pin "22") (pinfunction "VSYS_22") (pintype "passive"))
    )
    (net (code "69") (name "VSys1") (class "Default")
      (node (ref "C50E") (pin "1") (pinfunction "1_1") (pintype "passive"))
      (node (ref "C52E") (pin "1") (pinfunction "1_1") (pintype "passive"))
      (node (ref "C53E") (pin "1") (pinfunction "1_1") (pintype "passive"))
      (node (ref "C54E") (pin "1") (pinfunction "1_1") (pintype "passive"))
      (node (ref "C58E") (pin "1") (pinfunction "1_1") (pintype "passive"))
      (node (ref "FB1E") (pin "2") (pinfunction "2_2") (pintype "passive"))
      (node (ref "R46E") (pin "1") (pinfunction "1_1") (pintype "passive"))
      (node (ref "TP2E") (pin "1") (pinfunction "1_1") (pintype "passive"))
      (node (ref "U4E") (pin "3") (pinfunction "VIN_3") (pintype "passive"))
    )
    (net (code "70") (name "unconnected-(U2E-EN{slash}OTG-Pad5)") (class "Default")
      (node (ref "U2E") (pin "5") (pinfunction "EN/OTG_5") (pintype "passive+no_connect"))
    )
  )
)
